# LED_VCF.net
KiCad netlist of a schematic drawn in EAGLE
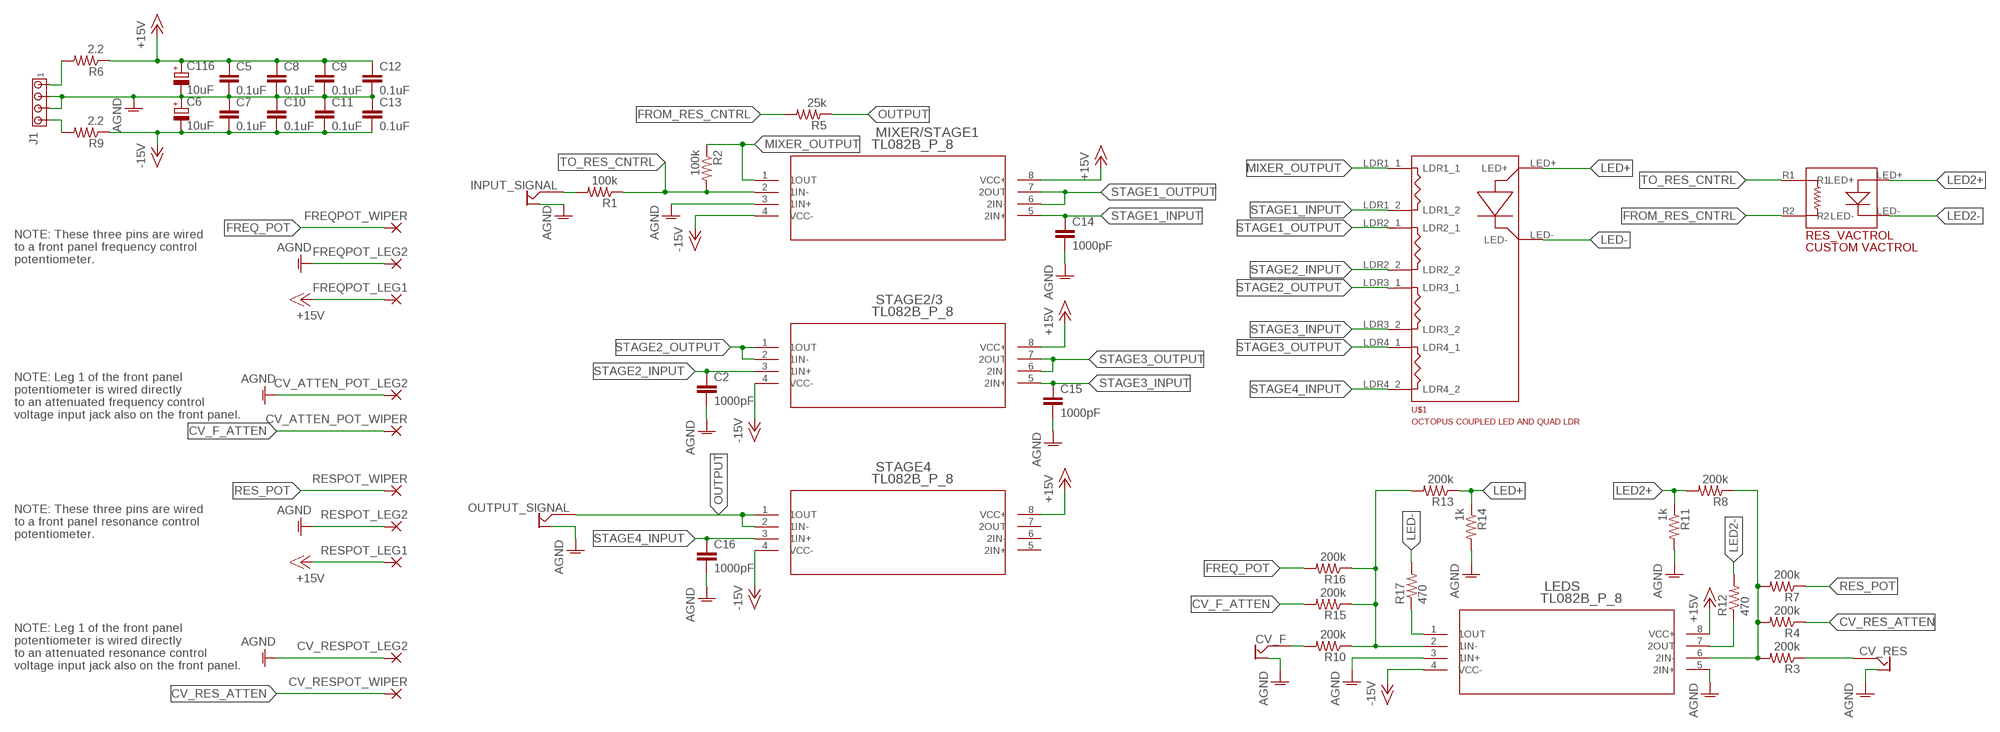
[diagram p0: schematic, sheet 1]

(export (version "E")
  (design (tool "Eeschema 10.0.6"))
  (components
    (comp (ref "C2")
      (value "1000pF")
      (footprint "eagle-import:AXIAL-5MM")
      (libsource (lib "eagle-import") (part "CAP_"))
    )
    (comp (ref "C5")
      (value "0.1uF")
      (footprint "eagle-import:AXIAL-5MM")
      (libsource (lib "eagle-import") (part "CAP_"))
    )
    (comp (ref "C6")
      (value "10uF")
      (footprint "eagle-import:E1,8-4")
      (libsource (lib "eagle-import") (part "CPOL-EUE1.8-4"))
    )
    (comp (ref "C7")
      (value "0.1uF")
      (footprint "eagle-import:AXIAL-5MM")
      (libsource (lib "eagle-import") (part "CAP_"))
    )
    (comp (ref "C8")
      (value "0.1uF")
      (footprint "eagle-import:AXIAL-5MM")
      (libsource (lib "eagle-import") (part "CAP_"))
    )
    (comp (ref "C9")
      (value "0.1uF")
      (footprint "eagle-import:AXIAL-5MM")
      (libsource (lib "eagle-import") (part "CAP_"))
    )
    (comp (ref "C10")
      (value "0.1uF")
      (footprint "eagle-import:AXIAL-5MM")
      (libsource (lib "eagle-import") (part "CAP_"))
    )
    (comp (ref "C11")
      (value "0.1uF")
      (footprint "eagle-import:AXIAL-5MM")
      (libsource (lib "eagle-import") (part "CAP_"))
    )
    (comp (ref "C12")
      (value "0.1uF")
      (footprint "eagle-import:AXIAL-5MM")
      (libsource (lib "eagle-import") (part "CAP_"))
    )
    (comp (ref "C13")
      (value "0.1uF")
      (footprint "eagle-import:AXIAL-5MM")
      (libsource (lib "eagle-import") (part "CAP_"))
    )
    (comp (ref "C14")
      (value "1000pF")
      (footprint "eagle-import:AXIAL-5MM")
      (libsource (lib "eagle-import") (part "CAP_"))
    )
    (comp (ref "C15")
      (value "1000pF")
      (footprint "eagle-import:AXIAL-5MM")
      (libsource (lib "eagle-import") (part "CAP_"))
    )
    (comp (ref "C16")
      (value "1000pF")
      (footprint "eagle-import:AXIAL-5MM")
      (libsource (lib "eagle-import") (part "CAP_"))
    )
    (comp (ref "C116")
      (value "10uF")
      (footprint "eagle-import:E1,8-4")
      (libsource (lib "eagle-import") (part "CPOL-EUE1.8-4"))
    )
    (comp (ref "CV_ATTEN_POT_LEG2")
      (value "IOPAD")
      (footprint "eagle-import:ELLIPTICALPADSINGLE")
      (libsource (lib "eagle-import") (part "IOPAD"))
    )
    (comp (ref "CV_ATTEN_POT_WIPER")
      (value "IOPAD")
      (footprint "eagle-import:ELLIPTICALPADSINGLE")
      (libsource (lib "eagle-import") (part "IOPAD"))
    )
    (comp (ref "CV_F")
      (value "OFFBOARD2JACK")
      (footprint "eagle-import:OFFBOARD2JACK")
      (libsource (lib "eagle-import") (part "OFFBOARD2JACK"))
    )
    (comp (ref "CV_RES")
      (value "OFFBOARD2JACK")
      (footprint "eagle-import:OFFBOARD2JACK")
      (libsource (lib "eagle-import") (part "OFFBOARD2JACK"))
    )
    (comp (ref "CV_RESPOT_LEG2")
      (value "IOPAD")
      (footprint "eagle-import:ELLIPTICALPADSINGLE")
      (libsource (lib "eagle-import") (part "IOPAD"))
    )
    (comp (ref "CV_RESPOT_WIPER")
      (value "IOPAD")
      (footprint "eagle-import:ELLIPTICALPADSINGLE")
      (libsource (lib "eagle-import") (part "IOPAD"))
    )
    (comp (ref "FREQPOT_LEG1")
      (value "IOPAD")
      (footprint "eagle-import:ELLIPTICALPADSINGLE")
      (libsource (lib "eagle-import") (part "IOPAD"))
    )
    (comp (ref "FREQPOT_LEG2")
      (value "IOPAD")
      (footprint "eagle-import:ELLIPTICALPADSINGLE")
      (libsource (lib "eagle-import") (part "IOPAD"))
    )
    (comp (ref "FREQPOT_WIPER")
      (value "IOPAD")
      (footprint "eagle-import:ELLIPTICALPADSINGLE")
      (libsource (lib "eagle-import") (part "IOPAD"))
    )
    (comp (ref "INPUT_SIGNAL")
      (value "OFFBOARD2JACK")
      (footprint "eagle-import:OFFBOARD2JACK")
      (libsource (lib "eagle-import") (part "OFFBOARD2JACK"))
    )
    (comp (ref "J1")
      (value "MTA04-156")
      (footprint "eagle-import:1X4MTA")
      (libsource (lib "eagle-import") (part "MTA04-156"))
    )
    (comp (ref "LEDS")
      (value "TL082B_P_8")
      (footprint "eagle-import:P8")
      (fields
        (field (name "GENERIC_PART_NUMBER") "TL082B")
        (field (name "MANUFACTURER") "Texas Instruments")
        (field (name "MANUFACTURER_PART_NUMBER") "tl082b_p_8")
      )
      (libsource (lib "eagle-import") (part "TL082B_P_8"))
    )
    (comp (ref "MIXER/STAGE1")
      (value "TL082B_P_8")
      (footprint "eagle-import:P8")
      (fields
        (field (name "GENERIC_PART_NUMBER") "TL082B")
        (field (name "MANUFACTURER") "Texas Instruments")
        (field (name "MANUFACTURER_PART_NUMBER") "tl082b_p_8")
      )
      (libsource (lib "eagle-import") (part "TL082B_P_8"))
    )
    (comp (ref "OUTPUT_SIGNAL")
      (value "OFFBOARD2JACK")
      (footprint "eagle-import:OFFBOARD2JACK")
      (libsource (lib "eagle-import") (part "OFFBOARD2JACK"))
    )
    (comp (ref "R1")
      (value "100k")
      (footprint "eagle-import:AXIAL-0.4")
      (libsource (lib "eagle-import") (part "RESISTORPTH-1/4W"))
    )
    (comp (ref "R2")
      (value "100k")
      (footprint "eagle-import:AXIAL-0.4")
      (libsource (lib "eagle-import") (part "RESISTORPTH-1/4W"))
    )
    (comp (ref "R3")
      (value "200k")
      (footprint "eagle-import:AXIAL-0.4")
      (libsource (lib "eagle-import") (part "RESISTORPTH-1/4W"))
    )
    (comp (ref "R4")
      (value "200k")
      (footprint "eagle-import:AXIAL-0.4")
      (libsource (lib "eagle-import") (part "RESISTORPTH-1/4W"))
    )
    (comp (ref "R5")
      (value "25k")
      (footprint "eagle-import:AXIAL-0.4")
      (libsource (lib "eagle-import") (part "RESISTORPTH-1/4W"))
    )
    (comp (ref "R6")
      (value "2.2")
      (footprint "eagle-import:AXIAL-0.4")
      (libsource (lib "eagle-import") (part "RESISTORPTH-1/4W"))
    )
    (comp (ref "R7")
      (value "200k")
      (footprint "eagle-import:AXIAL-0.4")
      (libsource (lib "eagle-import") (part "RESISTORPTH-1/4W"))
    )
    (comp (ref "R8")
      (value "200k")
      (footprint "eagle-import:AXIAL-0.4")
      (libsource (lib "eagle-import") (part "RESISTORPTH-1/4W"))
    )
    (comp (ref "R9")
      (value "2.2")
      (footprint "eagle-import:AXIAL-0.4")
      (libsource (lib "eagle-import") (part "RESISTORPTH-1/4W"))
    )
    (comp (ref "R10")
      (value "200k")
      (footprint "eagle-import:AXIAL-0.4")
      (libsource (lib "eagle-import") (part "RESISTORPTH-1/4W"))
    )
    (comp (ref "R11")
      (value "1k")
      (footprint "eagle-import:AXIAL-0.4")
      (libsource (lib "eagle-import") (part "RESISTORPTH-1/4W"))
    )
    (comp (ref "R12")
      (value "470")
      (footprint "eagle-import:AXIAL-0.4")
      (libsource (lib "eagle-import") (part "RESISTORPTH-1/4W"))
    )
    (comp (ref "R13")
      (value "200k")
      (footprint "eagle-import:AXIAL-0.4")
      (libsource (lib "eagle-import") (part "RESISTORPTH-1/4W"))
    )
    (comp (ref "R14")
      (value "1k")
      (footprint "eagle-import:AXIAL-0.4")
      (libsource (lib "eagle-import") (part "RESISTORPTH-1/4W"))
    )
    (comp (ref "R15")
      (value "200k")
      (footprint "eagle-import:AXIAL-0.4")
      (libsource (lib "eagle-import") (part "RESISTORPTH-1/4W"))
    )
    (comp (ref "R16")
      (value "200k")
      (footprint "eagle-import:AXIAL-0.4")
      (libsource (lib "eagle-import") (part "RESISTORPTH-1/4W"))
    )
    (comp (ref "R17")
      (value "470")
      (footprint "eagle-import:AXIAL-0.4")
      (libsource (lib "eagle-import") (part "RESISTORPTH-1/4W"))
    )
    (comp (ref "RESPOT_LEG1")
      (value "IOPAD")
      (footprint "eagle-import:ELLIPTICALPADSINGLE")
      (libsource (lib "eagle-import") (part "IOPAD"))
    )
    (comp (ref "RESPOT_LEG2")
      (value "IOPAD")
      (footprint "eagle-import:ELLIPTICALPADSINGLE")
      (libsource (lib "eagle-import") (part "IOPAD"))
    )
    (comp (ref "RESPOT_WIPER")
      (value "IOPAD")
      (footprint "eagle-import:ELLIPTICALPADSINGLE")
      (libsource (lib "eagle-import") (part "IOPAD"))
    )
    (comp (ref "RES_VACTROL")
      (value "CUSTOM_VACTROL_HAYDENTHROUGH-HOLE")
      (footprint "eagle-import:CUSTOM_VACTROL_HAYDEN")
      (libsource (lib "eagle-import") (part "CUSTOM_VACTROL_HAYDENTHROUGH-HOLE"))
    )
    (comp (ref "STAGE2/3")
      (value "TL082B_P_8")
      (footprint "eagle-import:P8")
      (fields
        (field (name "GENERIC_PART_NUMBER") "TL082B")
        (field (name "MANUFACTURER") "Texas Instruments")
        (field (name "MANUFACTURER_PART_NUMBER") "tl082b_p_8")
      )
      (libsource (lib "eagle-import") (part "TL082B_P_8"))
    )
    (comp (ref "STAGE4")
      (value "TL082B_P_8")
      (footprint "eagle-import:P8")
      (fields
        (field (name "GENERIC_PART_NUMBER") "TL082B")
        (field (name "MANUFACTURER") "Texas Instruments")
        (field (name "MANUFACTURER_PART_NUMBER") "tl082b_p_8")
      )
      (libsource (lib "eagle-import") (part "TL082B_P_8"))
    )
    (comp (ref "U$1")
      (value "OCTOPUS_LED_QUAD_LDRTHROUGH_HOLE")
      (footprint "eagle-import:OCTOPUS_LED_QUAD_LDR")
      (libsource (lib "eagle-import") (part "OCTOPUS_LED_QUAD_LDRTHROUGH_HOLE"))
    )
  )
  (nets
    (net (code "1") (name "+15V") (class "Default")
      (node (ref "C116") (pin "+") (pinfunction "+_+") (pintype "passive"))
      (node (ref "C12") (pin "P$1") (pinfunction "1_P$1") (pintype "passive"))
      (node (ref "C5") (pin "P$1") (pinfunction "1_P$1") (pintype "passive"))
      (node (ref "C8") (pin "P$1") (pinfunction "1_P$1") (pintype "passive"))
      (node (ref "C9") (pin "P$1") (pinfunction "1_P$1") (pintype "passive"))
      (node (ref "FREQPOT_LEG1") (pin "P$1") (pinfunction "P_P$1") (pintype "passive"))
      (node (ref "LEDS") (pin "8") (pinfunction "VCC+_8") (pintype "power_in"))
      (node (ref "MIXER/STAGE1") (pin "8") (pinfunction "VCC+_8") (pintype "power_in"))
      (node (ref "R6") (pin "P$1") (pinfunction "1_P$1") (pintype "passive"))
      (node (ref "RESPOT_LEG1") (pin "P$1") (pinfunction "P_P$1") (pintype "passive"))
      (node (ref "STAGE2/3") (pin "8") (pinfunction "VCC+_8") (pintype "power_in"))
      (node (ref "STAGE4") (pin "8") (pinfunction "VCC+_8") (pintype "power_in"))
    )
    (net (code "2") (name "-15V") (class "Default")
      (node (ref "C10") (pin "P$2") (pinfunction "2_P$2") (pintype "passive"))
      (node (ref "C11") (pin "P$2") (pinfunction "2_P$2") (pintype "passive"))
      (node (ref "C13") (pin "P$2") (pinfunction "2_P$2") (pintype "passive"))
      (node (ref "C6") (pin "-") (pinfunction "-_-") (pintype "passive"))
      (node (ref "C7") (pin "P$2") (pinfunction "2_P$2") (pintype "passive"))
      (node (ref "LEDS") (pin "4") (pinfunction "VCC-_4") (pintype "power_in"))
      (node (ref "MIXER/STAGE1") (pin "4") (pinfunction "VCC-_4") (pintype "power_in"))
      (node (ref "R9") (pin "P$1") (pinfunction "1_P$1") (pintype "passive"))
      (node (ref "STAGE2/3") (pin "4") (pinfunction "VCC-_4") (pintype "power_in"))
      (node (ref "STAGE4") (pin "4") (pinfunction "VCC-_4") (pintype "power_in"))
    )
    (net (code "3") (name "AGND") (class "Default")
      (node (ref "C10") (pin "P$1") (pinfunction "1_P$1") (pintype "passive"))
      (node (ref "C11") (pin "P$1") (pinfunction "1_P$1") (pintype "passive"))
      (node (ref "C116") (pin "-") (pinfunction "-_-") (pintype "passive"))
      (node (ref "C12") (pin "P$2") (pinfunction "2_P$2") (pintype "passive"))
      (node (ref "C13") (pin "P$1") (pinfunction "1_P$1") (pintype "passive"))
      (node (ref "C14") (pin "P$2") (pinfunction "2_P$2") (pintype "passive"))
      (node (ref "C15") (pin "P$2") (pinfunction "2_P$2") (pintype "passive"))
      (node (ref "C16") (pin "P$2") (pinfunction "2_P$2") (pintype "passive"))
      (node (ref "C2") (pin "P$2") (pinfunction "2_P$2") (pintype "passive"))
      (node (ref "C5") (pin "P$2") (pinfunction "2_P$2") (pintype "passive"))
      (node (ref "C6") (pin "+") (pinfunction "+_+") (pintype "passive"))
      (node (ref "C7") (pin "P$1") (pinfunction "1_P$1") (pintype "passive"))
      (node (ref "C8") (pin "P$2") (pinfunction "2_P$2") (pintype "passive"))
      (node (ref "C9") (pin "P$2") (pinfunction "2_P$2") (pintype "passive"))
      (node (ref "CV_ATTEN_POT_LEG2") (pin "P$1") (pinfunction "P_P$1") (pintype "passive"))
      (node (ref "CV_F") (pin "GND") (pinfunction "GND_GND") (pintype "passive"))
      (node (ref "CV_RES") (pin "GND") (pinfunction "GND_GND") (pintype "passive"))
      (node (ref "CV_RESPOT_LEG2") (pin "P$1") (pinfunction "P_P$1") (pintype "passive"))
      (node (ref "FREQPOT_LEG2") (pin "P$1") (pinfunction "P_P$1") (pintype "passive"))
      (node (ref "INPUT_SIGNAL") (pin "GND") (pinfunction "GND_GND") (pintype "passive"))
      (node (ref "J1") (pin "2") (pinfunction "2_2") (pintype "passive"))
      (node (ref "J1") (pin "3") (pinfunction "3_3") (pintype "passive"))
      (node (ref "LEDS") (pin "3") (pinfunction "1IN+_3") (pintype "input"))
      (node (ref "LEDS") (pin "5") (pinfunction "2IN+_5") (pintype "input"))
      (node (ref "MIXER/STAGE1") (pin "3") (pinfunction "1IN+_3") (pintype "input"))
      (node (ref "OUTPUT_SIGNAL") (pin "GND") (pinfunction "GND_GND") (pintype "passive"))
      (node (ref "R11") (pin "P$2") (pinfunction "2_P$2") (pintype "passive"))
      (node (ref "R14") (pin "P$2") (pinfunction "2_P$2") (pintype "passive"))
      (node (ref "RESPOT_LEG2") (pin "P$1") (pinfunction "P_P$1") (pintype "passive"))
    )
    (net (code "4") (name "CV_F_ATTEN") (class "Default")
      (node (ref "CV_ATTEN_POT_WIPER") (pin "P$1") (pinfunction "P_P$1") (pintype "passive"))
      (node (ref "R15") (pin "P$2") (pinfunction "2_P$2") (pintype "passive"))
    )
    (net (code "5") (name "CV_RES_ATTEN") (class "Default")
      (node (ref "CV_RESPOT_WIPER") (pin "P$1") (pinfunction "P_P$1") (pintype "passive"))
      (node (ref "R4") (pin "P$1") (pinfunction "1_P$1") (pintype "passive"))
    )
    (net (code "6") (name "FREQ_POT") (class "Default")
      (node (ref "FREQPOT_WIPER") (pin "P$1") (pinfunction "P_P$1") (pintype "passive"))
      (node (ref "R16") (pin "P$2") (pinfunction "2_P$2") (pintype "passive"))
    )
    (net (code "7") (name "FROM_RES_CNTRL") (class "Default")
      (node (ref "R5") (pin "P$2") (pinfunction "2_P$2") (pintype "passive"))
      (node (ref "RES_VACTROL") (pin "R2") (pinfunction "R2_R2") (pintype "bidirectional"))
    )
    (net (code "8") (name "LED+") (class "Default")
      (node (ref "R13") (pin "P$1") (pinfunction "1_P$1") (pintype "passive"))
      (node (ref "R14") (pin "P$1") (pinfunction "1_P$1") (pintype "passive"))
      (node (ref "U$1") (pin "LED+") (pinfunction "LED+_LED+") (pintype "bidirectional"))
    )
    (net (code "9") (name "LED-") (class "Default")
      (node (ref "R17") (pin "P$2") (pinfunction "2_P$2") (pintype "passive"))
      (node (ref "U$1") (pin "LED-") (pinfunction "LED-_LED-") (pintype "bidirectional"))
    )
    (net (code "10") (name "LED2+") (class "Default")
      (node (ref "R11") (pin "P$1") (pinfunction "1_P$1") (pintype "passive"))
      (node (ref "R8") (pin "P$2") (pinfunction "2_P$2") (pintype "passive"))
      (node (ref "RES_VACTROL") (pin "LED+") (pinfunction "LED+_LED+") (pintype "bidirectional"))
    )
    (net (code "11") (name "LED2-") (class "Default")
      (node (ref "R12") (pin "P$2") (pinfunction "2_P$2") (pintype "passive"))
      (node (ref "RES_VACTROL") (pin "LED-") (pinfunction "LED-_LED-") (pintype "bidirectional"))
    )
    (net (code "12") (name "MIXER_OUTPUT") (class "Default")
      (node (ref "MIXER/STAGE1") (pin "1") (pinfunction "1OUT_1") (pintype "output"))
      (node (ref "R2") (pin "P$1") (pinfunction "1_P$1") (pintype "passive"))
      (node (ref "U$1") (pin "LDR1_1") (pinfunction "LDR1_1_LDR1_1") (pintype "bidirectional"))
    )
    (net (code "13") (name "Net-(LEDS-1IN-)") (class "Default")
      (node (ref "LEDS") (pin "2") (pinfunction "1IN-_2") (pintype "input"))
      (node (ref "R10") (pin "P$1") (pinfunction "1_P$1") (pintype "passive"))
      (node (ref "R13") (pin "P$2") (pinfunction "2_P$2") (pintype "passive"))
      (node (ref "R15") (pin "P$1") (pinfunction "1_P$1") (pintype "passive"))
      (node (ref "R16") (pin "P$1") (pinfunction "1_P$1") (pintype "passive"))
    )
    (net (code "14") (name "Net-(LEDS-1OUT)") (class "Default")
      (node (ref "LEDS") (pin "1") (pinfunction "1OUT_1") (pintype "output"))
      (node (ref "R17") (pin "P$1") (pinfunction "1_P$1") (pintype "passive"))
    )
    (net (code "15") (name "Net-(LEDS-2IN-)") (class "Default")
      (node (ref "LEDS") (pin "6") (pinfunction "2IN-_6") (pintype "input"))
      (node (ref "R3") (pin "P$2") (pinfunction "2_P$2") (pintype "passive"))
      (node (ref "R4") (pin "P$2") (pinfunction "2_P$2") (pintype "passive"))
      (node (ref "R7") (pin "P$2") (pinfunction "2_P$2") (pintype "passive"))
      (node (ref "R8") (pin "P$1") (pinfunction "1_P$1") (pintype "passive"))
    )
    (net (code "16") (name "Net-(LEDS-2OUT)") (class "Default")
      (node (ref "LEDS") (pin "7") (pinfunction "2OUT_7") (pintype "output"))
      (node (ref "R12") (pin "P$1") (pinfunction "1_P$1") (pintype "passive"))
    )
    (net (code "17") (name "Net-(R1-2)") (class "Default")
      (node (ref "INPUT_SIGNAL") (pin "SIGNAL") (pinfunction "SIGNAL_SIGNAL") (pintype "passive"))
      (node (ref "R1") (pin "P$2") (pinfunction "2_P$2") (pintype "passive"))
    )
    (net (code "18") (name "Net-(R3-1)") (class "Default")
      (node (ref "CV_RES") (pin "SIGNAL") (pinfunction "SIGNAL_SIGNAL") (pintype "passive"))
      (node (ref "R3") (pin "P$1") (pinfunction "1_P$1") (pintype "passive"))
    )
    (net (code "19") (name "Net-(R6-2)") (class "Default")
      (node (ref "J1") (pin "1") (pinfunction "1_1") (pintype "passive"))
      (node (ref "R6") (pin "P$2") (pinfunction "2_P$2") (pintype "passive"))
    )
    (net (code "20") (name "Net-(R9-2)") (class "Default")
      (node (ref "J1") (pin "4") (pinfunction "4_4") (pintype "passive"))
      (node (ref "R9") (pin "P$2") (pinfunction "2_P$2") (pintype "passive"))
    )
    (net (code "21") (name "Net-(R10-2)") (class "Default")
      (node (ref "CV_F") (pin "SIGNAL") (pinfunction "SIGNAL_SIGNAL") (pintype "passive"))
      (node (ref "R10") (pin "P$2") (pinfunction "2_P$2") (pintype "passive"))
    )
    (net (code "22") (name "OUTPUT") (class "Default")
      (node (ref "OUTPUT_SIGNAL") (pin "SIGNAL") (pinfunction "SIGNAL_SIGNAL") (pintype "passive"))
      (node (ref "R5") (pin "P$1") (pinfunction "1_P$1") (pintype "passive"))
      (node (ref "STAGE4") (pin "1") (pinfunction "1OUT_1") (pintype "output"))
      (node (ref "STAGE4") (pin "2") (pinfunction "1IN-_2") (pintype "input"))
    )
    (net (code "23") (name "RES_POT") (class "Default")
      (node (ref "R7") (pin "P$1") (pinfunction "1_P$1") (pintype "passive"))
      (node (ref "RESPOT_WIPER") (pin "P$1") (pinfunction "P_P$1") (pintype "passive"))
    )
    (net (code "24") (name "STAGE1_INPUT") (class "Default")
      (node (ref "C14") (pin "P$1") (pinfunction "1_P$1") (pintype "passive"))
      (node (ref "MIXER/STAGE1") (pin "5") (pinfunction "2IN+_5") (pintype "input"))
      (node (ref "U$1") (pin "LDR1_2") (pinfunction "LDR1_2_LDR1_2") (pintype "bidirectional"))
    )
    (net (code "25") (name "STAGE1_OUTPUT") (class "Default")
      (node (ref "MIXER/STAGE1") (pin "6") (pinfunction "2IN-_6") (pintype "input"))
      (node (ref "MIXER/STAGE1") (pin "7") (pinfunction "2OUT_7") (pintype "output"))
      (node (ref "U$1") (pin "LDR2_1") (pinfunction "LDR2_1_LDR2_1") (pintype "bidirectional"))
    )
    (net (code "26") (name "STAGE2_INPUT") (class "Default")
      (node (ref "C2") (pin "P$1") (pinfunction "1_P$1") (pintype "passive"))
      (node (ref "STAGE2/3") (pin "3") (pinfunction "1IN+_3") (pintype "input"))
      (node (ref "U$1") (pin "LDR2_2") (pinfunction "LDR2_2_LDR2_2") (pintype "bidirectional"))
    )
    (net (code "27") (name "STAGE2_OUTPUT") (class "Default")
      (node (ref "STAGE2/3") (pin "1") (pinfunction "1OUT_1") (pintype "output"))
      (node (ref "STAGE2/3") (pin "2") (pinfunction "1IN-_2") (pintype "input"))
      (node (ref "U$1") (pin "LDR3_1") (pinfunction "LDR3_1_LDR3_1") (pintype "bidirectional"))
    )
    (net (code "28") (name "STAGE3_INPUT") (class "Default")
      (node (ref "C15") (pin "P$1") (pinfunction "1_P$1") (pintype "passive"))
      (node (ref "STAGE2/3") (pin "5") (pinfunction "2IN+_5") (pintype "input"))
      (node (ref "U$1") (pin "LDR3_2") (pinfunction "LDR3_2_LDR3_2") (pintype "bidirectional"))
    )
    (net (code "29") (name "STAGE3_OUTPUT") (class "Default")
      (node (ref "STAGE2/3") (pin "6") (pinfunction "2IN-_6") (pintype "input"))
      (node (ref "STAGE2/3") (pin "7") (pinfunction "2OUT_7") (pintype "output"))
      (node (ref "U$1") (pin "LDR4_1") (pinfunction "LDR4_1_LDR4_1") (pintype "bidirectional"))
    )
    (net (code "30") (name "STAGE4_INPUT") (class "Default")
      (node (ref "C16") (pin "P$1") (pinfunction "1_P$1") (pintype "passive"))
      (node (ref "STAGE4") (pin "3") (pinfunction "1IN+_3") (pintype "input"))
      (node (ref "U$1") (pin "LDR4_2") (pinfunction "LDR4_2_LDR4_2") (pintype "bidirectional"))
    )
    (net (code "31") (name "TO_RES_CNTRL") (class "Default")
      (node (ref "MIXER/STAGE1") (pin "2") (pinfunction "1IN-_2") (pintype "input"))
      (node (ref "R1") (pin "P$1") (pinfunction "1_P$1") (pintype "passive"))
      (node (ref "R2") (pin "P$2") (pinfunction "2_P$2") (pintype "passive"))
      (node (ref "RES_VACTROL") (pin "R1") (pinfunction "R1_R1") (pintype "bidirectional"))
    )
    (net (code "32") (name "unconnected-(STAGE4-2IN+-Pad5)") (class "Default")
      (node (ref "STAGE4") (pin "5") (pinfunction "2IN+_5") (pintype "input"))
    )
    (net (code "33") (name "unconnected-(STAGE4-2IN--Pad6)") (class "Default")
      (node (ref "STAGE4") (pin "6") (pinfunction "2IN-_6") (pintype "input"))
    )
    (net (code "34") (name "unconnected-(STAGE4-2OUT-Pad7)") (class "Default")
      (node (ref "STAGE4") (pin "7") (pinfunction "2OUT_7") (pintype "output"))
    )
  )
)
